# 1-Connectors.net
KiCad netlist of a schematic drawn in Altium Designer
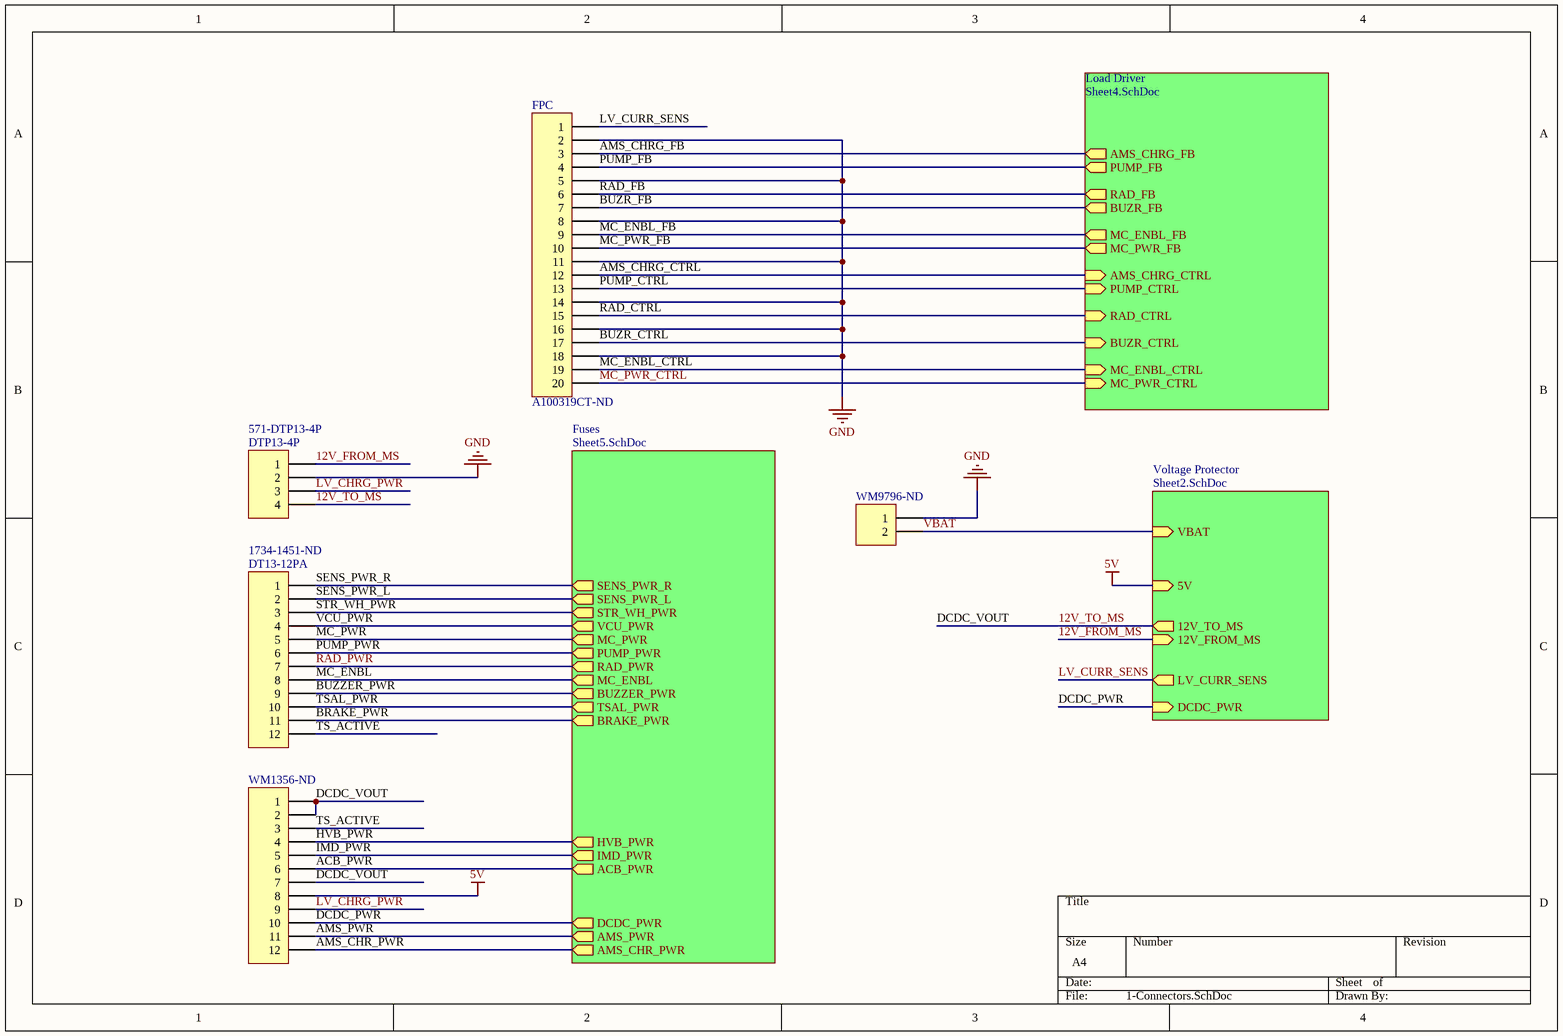
[diagram p0: 1-Connectors.SchDoc]

(export (version "E")
  (design (tool "Eeschema 10.0.6"))
  (components
    (comp (ref "DT13-12PA")
      (value "DT13-12PA")
      (footprint "DT13-12PA")
      (description "Header, 12-Pin")
      (fields
        (field (name "SUPPLIER PART NUMBER 1") "DT13-12PA")
        (field (name "SUPPLIER PART NUMBER 2") "1734-1451-ND")
        (field (name "PUBLISHER") "Altium Limited")
      )
      (libsource (lib "Power_PCB") (part "Header 12"))
    )
    (comp (ref "DTP13-4P")
      (value "DTP13-4P")
      (footprint "DTP13-4P")
      (description "Header, 4-Pin")
      (fields
        (field (name "SUPPLIER PART NUMBER 1") "571-DTP13-4P")
        (field (name "PUBLISHER") "Altium Limited")
      )
      (libsource (lib "Miscellaneous Connectors") (part "Header 4"))
    )
    (comp (ref "FPC")
      (value "Header 20")
      (footprint "A100319CT-ND")
      (description "Header, 20-Pin")
      (fields
        (field (name "SUPPLIER PART NUMBER 1") "A100319CT-ND")
        (field (name "PUBLISHER") "Altium Limited")
      )
      (libsource (lib "Miscellaneous Connectors") (part "Header 20"))
    )
    (comp (ref "WM1356-ND")
      (value "Header 12")
      (footprint "WM1356-ND")
      (description "Header, 12-Pin")
      (fields (field (name "SUPPLIER PART NUMBER 1") "WM1356-ND") (field (name "PUBLISHER") "Altium Limited"))
      (libsource (lib "Power_PCB") (part "Header 12"))
    )
    (comp (ref "WM9796-ND")
      (value "WM9796-ND")
      (footprint "WM9796-ND")
      (description "Header, 2-Pin")
      (fields (field (name "PUBLISHER") "Altium Limited"))
      (libsource (lib "Miscellaneous Connectors") (part "Header 2"))
    )
  )
  (nets
    (net (code "1") (name "/12V_FROM_MS") (class "Default")
      (node (ref "DTP13-4P") (pin "1") (pinfunction "1_1") (pintype "passive"))
    )
    (net (code "2") (name "/12V_TO_MS") (class "Default")
      (node (ref "DTP13-4P") (pin "4") (pinfunction "4_4") (pintype "passive"))
      (node (ref "WM1356-ND") (pin "1") (pinfunction "1_1") (pintype "passive"))
      (node (ref "WM1356-ND") (pin "2") (pinfunction "2_2") (pintype "passive"))
      (node (ref "WM1356-ND") (pin "7") (pinfunction "7_7") (pintype "passive"))
    )
    (net (code "3") (name "/ACB_PWR") (class "Default")
      (node (ref "WM1356-ND") (pin "6") (pinfunction "6_6") (pintype "passive"))
    )
    (net (code "4") (name "/AMS_CHRG_CTRL") (class "Default")
      (node (ref "FPC") (pin "12") (pinfunction "12_12") (pintype "passive"))
    )
    (net (code "5") (name "/AMS_CHRG_FB") (class "Default")
      (node (ref "FPC") (pin "3") (pinfunction "3_3") (pintype "passive"))
    )
    (net (code "6") (name "/AMS_CHR_PWR") (class "Default")
      (node (ref "WM1356-ND") (pin "12") (pinfunction "12_12") (pintype "passive"))
    )
    (net (code "7") (name "/AMS_PWR") (class "Default")
      (node (ref "WM1356-ND") (pin "11") (pinfunction "11_11") (pintype "passive"))
    )
    (net (code "8") (name "/BRAKE_PWR") (class "Default")
      (node (ref "DT13-12PA") (pin "11") (pinfunction "11_11") (pintype "passive"))
    )
    (net (code "9") (name "/BUZR_CTRL") (class "Default")
      (node (ref "FPC") (pin "17") (pinfunction "17_17") (pintype "passive"))
    )
    (net (code "10") (name "/BUZR_FB") (class "Default")
      (node (ref "FPC") (pin "7") (pinfunction "7_7") (pintype "passive"))
    )
    (net (code "11") (name "/BUZZER_PWR") (class "Default")
      (node (ref "DT13-12PA") (pin "9") (pinfunction "9_9") (pintype "passive"))
    )
    (net (code "12") (name "/DCDC_PWR") (class "Default")
      (node (ref "WM1356-ND") (pin "10") (pinfunction "10_10") (pintype "passive"))
    )
    (net (code "13") (name "/HVB_PWR") (class "Default")
      (node (ref "WM1356-ND") (pin "4") (pinfunction "4_4") (pintype "passive"))
    )
    (net (code "14") (name "/IMD_PWR") (class "Default")
      (node (ref "WM1356-ND") (pin "5") (pinfunction "5_5") (pintype "passive"))
    )
    (net (code "15") (name "/LV_CHRG_PWR") (class "Default")
      (node (ref "DTP13-4P") (pin "3") (pinfunction "3_3") (pintype "passive"))
      (node (ref "WM1356-ND") (pin "9") (pinfunction "9_9") (pintype "passive"))
    )
    (net (code "16") (name "/LV_CURR_SENS") (class "Default")
      (node (ref "FPC") (pin "1") (pinfunction "1_1") (pintype "passive"))
    )
    (net (code "17") (name "/MC_ENBL") (class "Default")
      (node (ref "DT13-12PA") (pin "8") (pinfunction "8_8") (pintype "passive"))
    )
    (net (code "18") (name "/MC_ENBL_CTRL") (class "Default")
      (node (ref "FPC") (pin "19") (pinfunction "19_19") (pintype "passive"))
    )
    (net (code "19") (name "/MC_ENBL_FB") (class "Default")
      (node (ref "FPC") (pin "9") (pinfunction "9_9") (pintype "passive"))
    )
    (net (code "20") (name "/MC_PWR") (class "Default")
      (node (ref "DT13-12PA") (pin "5") (pinfunction "5_5") (pintype "passive"))
    )
    (net (code "21") (name "/MC_PWR_CTRL") (class "Default")
      (node (ref "FPC") (pin "20") (pinfunction "20_20") (pintype "passive"))
    )
    (net (code "22") (name "/MC_PWR_FB") (class "Default")
      (node (ref "FPC") (pin "10") (pinfunction "10_10") (pintype "passive"))
    )
    (net (code "23") (name "/PUMP_CTRL") (class "Default")
      (node (ref "FPC") (pin "13") (pinfunction "13_13") (pintype "passive"))
    )
    (net (code "24") (name "/PUMP_FB") (class "Default")
      (node (ref "FPC") (pin "4") (pinfunction "4_4") (pintype "passive"))
    )
    (net (code "25") (name "/PUMP_PWR") (class "Default")
      (node (ref "DT13-12PA") (pin "6") (pinfunction "6_6") (pintype "passive"))
    )
    (net (code "26") (name "/RAD_CTRL") (class "Default")
      (node (ref "FPC") (pin "15") (pinfunction "15_15") (pintype "passive"))
    )
    (net (code "27") (name "/RAD_FB") (class "Default")
      (node (ref "FPC") (pin "6") (pinfunction "6_6") (pintype "passive"))
    )
    (net (code "28") (name "/RAD_PWR") (class "Default")
      (node (ref "DT13-12PA") (pin "7") (pinfunction "7_7") (pintype "passive"))
    )
    (net (code "29") (name "/SENS_PWR_L") (class "Default")
      (node (ref "DT13-12PA") (pin "2") (pinfunction "2_2") (pintype "passive"))
    )
    (net (code "30") (name "/SENS_PWR_R") (class "Default")
      (node (ref "DT13-12PA") (pin "1") (pinfunction "1_1") (pintype "passive"))
    )
    (net (code "31") (name "/STR_WH_PWR") (class "Default")
      (node (ref "DT13-12PA") (pin "3") (pinfunction "3_3") (pintype "passive"))
    )
    (net (code "32") (name "/TSAL_PWR") (class "Default")
      (node (ref "DT13-12PA") (pin "10") (pinfunction "10_10") (pintype "passive"))
    )
    (net (code "33") (name "/TS_ACTIVE") (class "Default")
      (node (ref "DT13-12PA") (pin "12") (pinfunction "12_12") (pintype "passive"))
      (node (ref "WM1356-ND") (pin "3") (pinfunction "3_3") (pintype "passive"))
    )
    (net (code "34") (name "/VBAT") (class "Default")
      (node (ref "WM9796-ND") (pin "2") (pinfunction "2_2") (pintype "passive"))
    )
    (net (code "35") (name "/VCU_PWR") (class "Default")
      (node (ref "DT13-12PA") (pin "4") (pinfunction "4_4") (pintype "passive"))
    )
    (net (code "36") (name "5V") (class "Default")
      (node (ref "WM1356-ND") (pin "8") (pinfunction "8_8") (pintype "passive"))
    )
    (net (code "37") (name "GND") (class "Default")
      (node (ref "DTP13-4P") (pin "2") (pinfunction "2_2") (pintype "passive"))
      (node (ref "FPC") (pin "11") (pinfunction "11_11") (pintype "passive"))
      (node (ref "FPC") (pin "14") (pinfunction "14_14") (pintype "passive"))
      (node (ref "FPC") (pin "16") (pinfunction "16_16") (pintype "passive"))
      (node (ref "FPC") (pin "18") (pinfunction "18_18") (pintype "passive"))
      (node (ref "FPC") (pin "2") (pinfunction "2_2") (pintype "passive"))
      (node (ref "FPC") (pin "5") (pinfunction "5_5") (pintype "passive"))
      (node (ref "FPC") (pin "8") (pinfunction "8_8") (pintype "passive"))
      (node (ref "WM9796-ND") (pin "1") (pinfunction "1_1") (pintype "passive"))
    )
  )
)
